# jtag-20-6.net
KiCad netlist of a schematic drawn in EAGLE
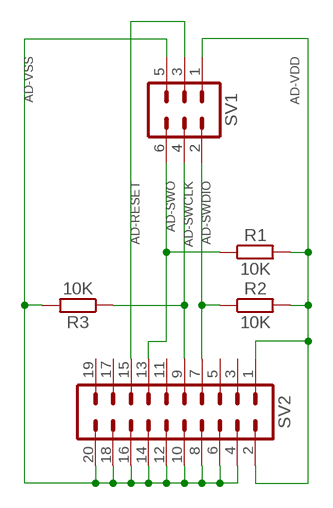
[diagram p0: schematic, sheet 1]

(export (version "E")
  (design (tool "Eeschema 10.0.6"))
  (components
    (comp (ref "R1")
      (value "10K")
      (footprint "eagle-import:R1206")
      (libsource (lib "eagle-import") (part "R-EU_R1206"))
    )
    (comp (ref "R2")
      (value "10K")
      (footprint "eagle-import:R1206")
      (libsource (lib "eagle-import") (part "R-EU_R1206"))
    )
    (comp (ref "R3")
      (value "10K")
      (footprint "eagle-import:R1206")
      (libsource (lib "eagle-import") (part "R-EU_R1206"))
    )
    (comp (ref "SV1")
      (value "MA03-2")
      (footprint "eagle-import:MA03-2")
      (libsource (lib "eagle-import") (part "MA03-2"))
    )
    (comp (ref "SV2")
      (value "MA10-2")
      (footprint "eagle-import:MA10-2")
      (libsource (lib "eagle-import") (part "MA10-2"))
    )
  )
  (nets
    (net (code "1") (name "/AD-RESET") (class "Default")
      (node (ref "SV1") (pin "3") (pinfunction "3_3") (pintype "passive"))
      (node (ref "SV2") (pin "15") (pinfunction "15_15") (pintype "passive"))
    )
    (net (code "2") (name "/AD-SWCLK") (class "Default")
      (node (ref "R3") (pin "1") (pinfunction "1_1") (pintype "passive"))
      (node (ref "SV1") (pin "4") (pinfunction "4_4") (pintype "passive"))
      (node (ref "SV2") (pin "9") (pinfunction "9_9") (pintype "passive"))
    )
    (net (code "3") (name "/AD-SWDIO") (class "Default")
      (node (ref "R2") (pin "1") (pinfunction "1_1") (pintype "passive"))
      (node (ref "SV1") (pin "2") (pinfunction "2_2") (pintype "passive"))
      (node (ref "SV2") (pin "7") (pinfunction "7_7") (pintype "passive"))
    )
    (net (code "4") (name "/AD-SWO") (class "Default")
      (node (ref "R1") (pin "1") (pinfunction "1_1") (pintype "passive"))
      (node (ref "SV1") (pin "6") (pinfunction "6_6") (pintype "passive"))
      (node (ref "SV2") (pin "13") (pinfunction "13_13") (pintype "passive"))
    )
    (net (code "5") (name "/AD-VDD") (class "Default")
      (node (ref "R1") (pin "2") (pinfunction "2_2") (pintype "passive"))
      (node (ref "R2") (pin "2") (pinfunction "2_2") (pintype "passive"))
      (node (ref "SV1") (pin "1") (pinfunction "1_1") (pintype "passive"))
      (node (ref "SV2") (pin "1") (pinfunction "1_1") (pintype "passive"))
      (node (ref "SV2") (pin "2") (pinfunction "2_2") (pintype "passive"))
    )
    (net (code "6") (name "/AD-VSS") (class "Default")
      (node (ref "R3") (pin "2") (pinfunction "2_2") (pintype "passive"))
      (node (ref "SV1") (pin "5") (pinfunction "5_5") (pintype "passive"))
      (node (ref "SV2") (pin "10") (pinfunction "10_10") (pintype "passive"))
      (node (ref "SV2") (pin "12") (pinfunction "12_12") (pintype "passive"))
      (node (ref "SV2") (pin "14") (pinfunction "14_14") (pintype "passive"))
      (node (ref "SV2") (pin "16") (pinfunction "16_16") (pintype "passive"))
      (node (ref "SV2") (pin "18") (pinfunction "18_18") (pintype "passive"))
      (node (ref "SV2") (pin "20") (pinfunction "20_20") (pintype "passive"))
      (node (ref "SV2") (pin "4") (pinfunction "4_4") (pintype "passive"))
      (node (ref "SV2") (pin "6") (pinfunction "6_6") (pintype "passive"))
      (node (ref "SV2") (pin "8") (pinfunction "8_8") (pintype "passive"))
    )
    (net (code "7") (name "unconnected-(SV2-Pad3)") (class "Default")
      (node (ref "SV2") (pin "3") (pinfunction "3_3") (pintype "passive"))
    )
    (net (code "8") (name "unconnected-(SV2-Pad5)") (class "Default")
      (node (ref "SV2") (pin "5") (pinfunction "5_5") (pintype "passive"))
    )
    (net (code "9") (name "unconnected-(SV2-Pad11)") (class "Default")
      (node (ref "SV2") (pin "11") (pinfunction "11_11") (pintype "passive"))
    )
    (net (code "10") (name "unconnected-(SV2-Pad17)") (class "Default")
      (node (ref "SV2") (pin "17") (pinfunction "17_17") (pintype "passive"))
    )
    (net (code "11") (name "unconnected-(SV2-Pad19)") (class "Default")
      (node (ref "SV2") (pin "19") (pinfunction "19_19") (pintype "passive"))
    )
  )
)
